# pcb_v2.net
KiCad netlist of a schematic drawn in EAGLE
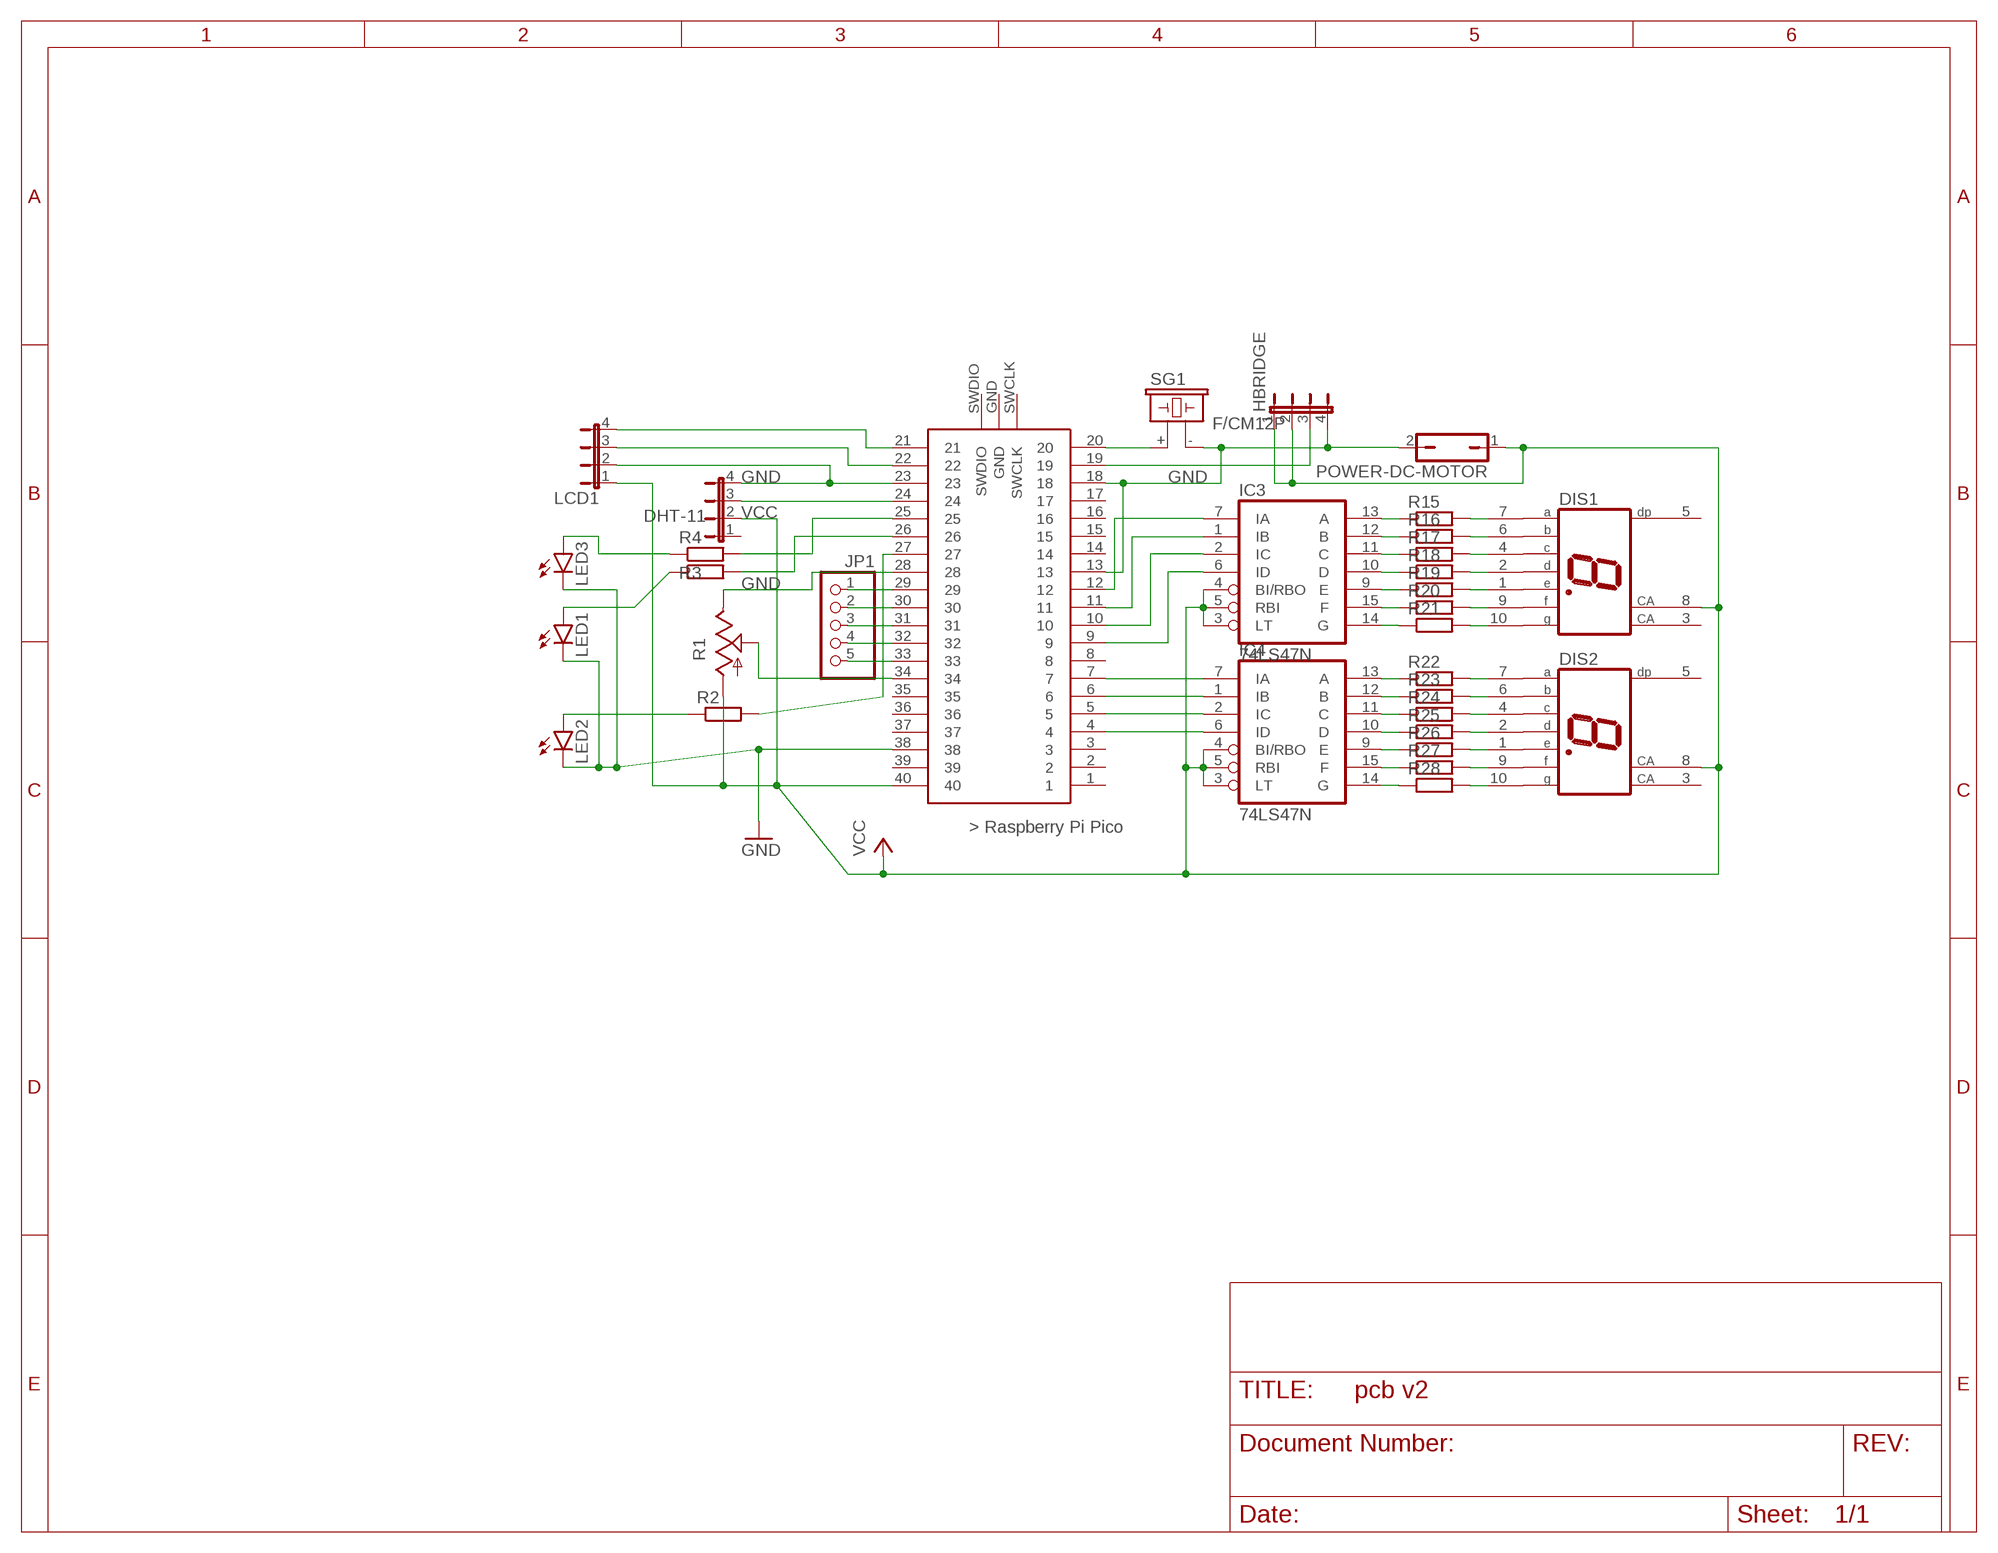
[diagram p0: schematic, sheet 1]

(export (version "E")
  (design (tool "Eeschema 10.0.6"))
  (components
    (comp (ref "DHT-11")
      (value "JP4E")
      (footprint "eagle-import:JP4")
      (libsource (lib "eagle-import") (part "JP4E"))
    )
    (comp (ref "DIS1")
      (value "HD-H101")
      (footprint "eagle-import:HDSP-M")
      (libsource (lib "eagle-import") (part "HD-H101"))
    )
    (comp (ref "DIS2")
      (value "HD-H101")
      (footprint "eagle-import:HDSP-M")
      (libsource (lib "eagle-import") (part "HD-H101"))
    )
    (comp (ref "HBRIDGE")
      (value "JP4E")
      (footprint "eagle-import:JP4")
      (libsource (lib "eagle-import") (part "JP4E"))
    )
    (comp (ref "IC3")
      (value "74LS47N")
      (footprint "eagle-import:DIL16")
      (libsource (lib "eagle-import") (part "7447NLS"))
    )
    (comp (ref "IC4")
      (value "74LS47N")
      (footprint "eagle-import:DIL16")
      (libsource (lib "eagle-import") (part "7447NLS"))
    )
    (comp (ref "JP1")
      (value "PINHD-1X5")
      (footprint "eagle-import:1X05")
      (libsource (lib "eagle-import") (part "PINHD-1X5"))
    )
    (comp (ref "LCD1")
      (value "JP4E")
      (footprint "eagle-import:JP4")
      (libsource (lib "eagle-import") (part "JP4E"))
    )
    (comp (ref "LED1")
      (value "LED5MM")
      (footprint "eagle-import:LED5MM")
      (libsource (lib "eagle-import") (part "LED5MM"))
    )
    (comp (ref "LED2")
      (value "LED5MM")
      (footprint "eagle-import:LED5MM")
      (libsource (lib "eagle-import") (part "LED5MM"))
    )
    (comp (ref "LED3")
      (value "LED5MM")
      (footprint "eagle-import:LED5MM")
      (libsource (lib "eagle-import") (part "LED5MM"))
    )
    (comp (ref "POWER-DC-MOTOR")
      (value "JP1Q")
      (footprint "eagle-import:JP1")
      (libsource (lib "eagle-import") (part "JP1Q"))
    )
    (comp (ref "R1")
      (value "TRIM_US-CA6V")
      (footprint "eagle-import:CA6V")
      (libsource (lib "eagle-import") (part "TRIM_US-CA6V"))
    )
    (comp (ref "R2")
      (value "R-EU_0207/10")
      (footprint "eagle-import:0207_10")
      (libsource (lib "eagle-import") (part "R-EU_0207/10"))
    )
    (comp (ref "R3")
      (value "R-EU_0207/10")
      (footprint "eagle-import:0207_10")
      (libsource (lib "eagle-import") (part "R-EU_0207/10"))
    )
    (comp (ref "R4")
      (value "R-EU_0207/10")
      (footprint "eagle-import:0207_10")
      (libsource (lib "eagle-import") (part "R-EU_0207/10"))
    )
    (comp (ref "R15")
      (value "R-EU_0207/12")
      (footprint "eagle-import:0207_12")
      (libsource (lib "eagle-import") (part "R-EU_0207/12"))
    )
    (comp (ref "R16")
      (value "R-EU_0207/12")
      (footprint "eagle-import:0207_12")
      (libsource (lib "eagle-import") (part "R-EU_0207/12"))
    )
    (comp (ref "R17")
      (value "R-EU_0207/12")
      (footprint "eagle-import:0207_12")
      (libsource (lib "eagle-import") (part "R-EU_0207/12"))
    )
    (comp (ref "R18")
      (value "R-EU_0207/12")
      (footprint "eagle-import:0207_12")
      (libsource (lib "eagle-import") (part "R-EU_0207/12"))
    )
    (comp (ref "R19")
      (value "R-EU_0207/12")
      (footprint "eagle-import:0207_12")
      (libsource (lib "eagle-import") (part "R-EU_0207/12"))
    )
    (comp (ref "R20")
      (value "R-EU_0207/12")
      (footprint "eagle-import:0207_12")
      (libsource (lib "eagle-import") (part "R-EU_0207/12"))
    )
    (comp (ref "R21")
      (value "R-EU_0207/12")
      (footprint "eagle-import:0207_12")
      (libsource (lib "eagle-import") (part "R-EU_0207/12"))
    )
    (comp (ref "R22")
      (value "R-EU_0207/12")
      (footprint "eagle-import:0207_12")
      (libsource (lib "eagle-import") (part "R-EU_0207/12"))
    )
    (comp (ref "R23")
      (value "R-EU_0207/12")
      (footprint "eagle-import:0207_12")
      (libsource (lib "eagle-import") (part "R-EU_0207/12"))
    )
    (comp (ref "R24")
      (value "R-EU_0207/12")
      (footprint "eagle-import:0207_12")
      (libsource (lib "eagle-import") (part "R-EU_0207/12"))
    )
    (comp (ref "R25")
      (value "R-EU_0207/12")
      (footprint "eagle-import:0207_12")
      (libsource (lib "eagle-import") (part "R-EU_0207/12"))
    )
    (comp (ref "R26")
      (value "R-EU_0207/12")
      (footprint "eagle-import:0207_12")
      (libsource (lib "eagle-import") (part "R-EU_0207/12"))
    )
    (comp (ref "R27")
      (value "R-EU_0207/12")
      (footprint "eagle-import:0207_12")
      (libsource (lib "eagle-import") (part "R-EU_0207/12"))
    )
    (comp (ref "R28")
      (value "R-EU_0207/12")
      (footprint "eagle-import:0207_12")
      (libsource (lib "eagle-import") (part "R-EU_0207/12"))
    )
    (comp (ref "SG1")
      (value "F/CM12P")
      (footprint "eagle-import:F_CM12P")
      (libsource (lib "eagle-import") (part "F/CM12P"))
    )
    (comp (ref "U$1")
      (value "RASPBERRY-PI-PICO_TH")
      (footprint "eagle-import:FT_RASPBERRY-PI-PICO_TH")
      (libsource (lib "eagle-import") (part "RASPBERRY-PI-PICO_TH"))
    )
  )
  (nets
    (net (code "1") (name "GND") (class "Default")
      (node (ref "DHT-11") (pin "4") (pinfunction "4_4") (pintype "passive"))
      (node (ref "HBRIDGE") (pin "4") (pinfunction "4_4") (pintype "passive"))
      (node (ref "LCD1") (pin "2") (pinfunction "2_2") (pintype "passive"))
      (node (ref "LED1") (pin "K") (pinfunction "C_K") (pintype "passive"))
      (node (ref "LED2") (pin "K") (pinfunction "C_K") (pintype "passive"))
      (node (ref "LED3") (pin "K") (pinfunction "C_K") (pintype "passive"))
      (node (ref "POWER-DC-MOTOR") (pin "2") (pinfunction "2_2") (pintype "passive"))
      (node (ref "R1") (pin "E") (pinfunction "E_E") (pintype "passive"))
      (node (ref "SG1") (pin "-") (pinfunction "2_-") (pintype "passive"))
      (node (ref "U$1") (pin "13") (pinfunction "13_13") (pintype "bidirectional"))
      (node (ref "U$1") (pin "18") (pinfunction "18_18") (pintype "bidirectional"))
      (node (ref "U$1") (pin "23") (pinfunction "23_23") (pintype "bidirectional"))
      (node (ref "U$1") (pin "28") (pinfunction "28_28") (pintype "bidirectional"))
      (node (ref "U$1") (pin "38") (pinfunction "38_38") (pintype "bidirectional"))
    )
    (net (code "2") (name "Net-(DHT-11-Pad3)") (class "Default")
      (node (ref "DHT-11") (pin "3") (pinfunction "3_3") (pintype "passive"))
      (node (ref "U$1") (pin "24") (pinfunction "24_24") (pintype "bidirectional"))
    )
    (net (code "3") (name "Net-(DIS1-A)") (class "Default")
      (node (ref "DIS1") (pin "7") (pinfunction "A_7") (pintype "passive"))
      (node (ref "R15") (pin "2") (pinfunction "2_2") (pintype "passive"))
    )
    (net (code "4") (name "Net-(DIS1-B)") (class "Default")
      (node (ref "DIS1") (pin "6") (pinfunction "B_6") (pintype "passive"))
      (node (ref "R16") (pin "2") (pinfunction "2_2") (pintype "passive"))
    )
    (net (code "5") (name "Net-(DIS1-C)") (class "Default")
      (node (ref "DIS1") (pin "4") (pinfunction "C_4") (pintype "passive"))
      (node (ref "R17") (pin "2") (pinfunction "2_2") (pintype "passive"))
    )
    (net (code "6") (name "Net-(DIS1-D)") (class "Default")
      (node (ref "DIS1") (pin "2") (pinfunction "D_2") (pintype "passive"))
      (node (ref "R18") (pin "2") (pinfunction "2_2") (pintype "passive"))
    )
    (net (code "7") (name "Net-(DIS1-E)") (class "Default")
      (node (ref "DIS1") (pin "1") (pinfunction "E_1") (pintype "passive"))
      (node (ref "R19") (pin "2") (pinfunction "2_2") (pintype "passive"))
    )
    (net (code "8") (name "Net-(DIS1-F)") (class "Default")
      (node (ref "DIS1") (pin "9") (pinfunction "F_9") (pintype "passive"))
      (node (ref "R20") (pin "2") (pinfunction "2_2") (pintype "passive"))
    )
    (net (code "9") (name "Net-(DIS1-G)") (class "Default")
      (node (ref "DIS1") (pin "10") (pinfunction "G_10") (pintype "passive"))
      (node (ref "R21") (pin "2") (pinfunction "2_2") (pintype "passive"))
    )
    (net (code "10") (name "Net-(DIS2-A)") (class "Default")
      (node (ref "DIS2") (pin "7") (pinfunction "A_7") (pintype "passive"))
      (node (ref "R22") (pin "2") (pinfunction "2_2") (pintype "passive"))
    )
    (net (code "11") (name "Net-(DIS2-B)") (class "Default")
      (node (ref "DIS2") (pin "6") (pinfunction "B_6") (pintype "passive"))
      (node (ref "R23") (pin "2") (pinfunction "2_2") (pintype "passive"))
    )
    (net (code "12") (name "Net-(DIS2-C)") (class "Default")
      (node (ref "DIS2") (pin "4") (pinfunction "C_4") (pintype "passive"))
      (node (ref "R24") (pin "2") (pinfunction "2_2") (pintype "passive"))
    )
    (net (code "13") (name "Net-(DIS2-D)") (class "Default")
      (node (ref "DIS2") (pin "2") (pinfunction "D_2") (pintype "passive"))
      (node (ref "R25") (pin "2") (pinfunction "2_2") (pintype "passive"))
    )
    (net (code "14") (name "Net-(DIS2-E)") (class "Default")
      (node (ref "DIS2") (pin "1") (pinfunction "E_1") (pintype "passive"))
      (node (ref "R26") (pin "2") (pinfunction "2_2") (pintype "passive"))
    )
    (net (code "15") (name "Net-(DIS2-F)") (class "Default")
      (node (ref "DIS2") (pin "9") (pinfunction "F_9") (pintype "passive"))
      (node (ref "R27") (pin "2") (pinfunction "2_2") (pintype "passive"))
    )
    (net (code "16") (name "Net-(DIS2-G)") (class "Default")
      (node (ref "DIS2") (pin "10") (pinfunction "G_10") (pintype "passive"))
      (node (ref "R28") (pin "2") (pinfunction "2_2") (pintype "passive"))
    )
    (net (code "17") (name "Net-(HBRIDGE-Pad3)") (class "Default")
      (node (ref "HBRIDGE") (pin "3") (pinfunction "3_3") (pintype "passive"))
      (node (ref "U$1") (pin "19") (pinfunction "19_19") (pintype "bidirectional"))
    )
    (net (code "18") (name "Net-(IC3A-A)") (class "Default")
      (node (ref "IC3") (pin "13") (pinfunction "A_13") (pintype "output"))
      (node (ref "R15") (pin "1") (pinfunction "1_1") (pintype "passive"))
    )
    (net (code "19") (name "Net-(IC3A-B)") (class "Default")
      (node (ref "IC3") (pin "12") (pinfunction "B_12") (pintype "output"))
      (node (ref "R16") (pin "1") (pinfunction "1_1") (pintype "passive"))
    )
    (net (code "20") (name "Net-(IC3A-C)") (class "Default")
      (node (ref "IC3") (pin "11") (pinfunction "C_11") (pintype "output"))
      (node (ref "R17") (pin "1") (pinfunction "1_1") (pintype "passive"))
    )
    (net (code "21") (name "Net-(IC3A-D)") (class "Default")
      (node (ref "IC3") (pin "10") (pinfunction "D_10") (pintype "output"))
      (node (ref "R18") (pin "1") (pinfunction "1_1") (pintype "passive"))
    )
    (net (code "22") (name "Net-(IC3A-E)") (class "Default")
      (node (ref "IC3") (pin "9") (pinfunction "E_9") (pintype "output"))
      (node (ref "R19") (pin "1") (pinfunction "1_1") (pintype "passive"))
    )
    (net (code "23") (name "Net-(IC3A-F)") (class "Default")
      (node (ref "IC3") (pin "15") (pinfunction "F_15") (pintype "output"))
      (node (ref "R20") (pin "1") (pinfunction "1_1") (pintype "passive"))
    )
    (net (code "24") (name "Net-(IC3A-G)") (class "Default")
      (node (ref "IC3") (pin "14") (pinfunction "G_14") (pintype "output"))
      (node (ref "R21") (pin "1") (pinfunction "1_1") (pintype "passive"))
    )
    (net (code "25") (name "Net-(IC3A-IA)") (class "Default")
      (node (ref "IC3") (pin "7") (pinfunction "IA_7") (pintype "input"))
      (node (ref "U$1") (pin "12") (pinfunction "12_12") (pintype "bidirectional"))
    )
    (net (code "26") (name "Net-(IC3A-IB)") (class "Default")
      (node (ref "IC3") (pin "1") (pinfunction "IB_1") (pintype "input"))
      (node (ref "U$1") (pin "11") (pinfunction "11_11") (pintype "bidirectional"))
    )
    (net (code "27") (name "Net-(IC3A-IC)") (class "Default")
      (node (ref "IC3") (pin "2") (pinfunction "IC_2") (pintype "input"))
      (node (ref "U$1") (pin "10") (pinfunction "10_10") (pintype "bidirectional"))
    )
    (net (code "28") (name "Net-(IC3A-ID)") (class "Default")
      (node (ref "IC3") (pin "6") (pinfunction "ID_6") (pintype "input"))
      (node (ref "U$1") (pin "9") (pinfunction "9_9") (pintype "bidirectional"))
    )
    (net (code "29") (name "Net-(IC4A-A)") (class "Default")
      (node (ref "IC4") (pin "13") (pinfunction "A_13") (pintype "output"))
      (node (ref "R22") (pin "1") (pinfunction "1_1") (pintype "passive"))
    )
    (net (code "30") (name "Net-(IC4A-B)") (class "Default")
      (node (ref "IC4") (pin "12") (pinfunction "B_12") (pintype "output"))
      (node (ref "R23") (pin "1") (pinfunction "1_1") (pintype "passive"))
    )
    (net (code "31") (name "Net-(IC4A-C)") (class "Default")
      (node (ref "IC4") (pin "11") (pinfunction "C_11") (pintype "output"))
      (node (ref "R24") (pin "1") (pinfunction "1_1") (pintype "passive"))
    )
    (net (code "32") (name "Net-(IC4A-D)") (class "Default")
      (node (ref "IC4") (pin "10") (pinfunction "D_10") (pintype "output"))
      (node (ref "R25") (pin "1") (pinfunction "1_1") (pintype "passive"))
    )
    (net (code "33") (name "Net-(IC4A-E)") (class "Default")
      (node (ref "IC4") (pin "9") (pinfunction "E_9") (pintype "output"))
      (node (ref "R26") (pin "1") (pinfunction "1_1") (pintype "passive"))
    )
    (net (code "34") (name "Net-(IC4A-F)") (class "Default")
      (node (ref "IC4") (pin "15") (pinfunction "F_15") (pintype "output"))
      (node (ref "R27") (pin "1") (pinfunction "1_1") (pintype "passive"))
    )
    (net (code "35") (name "Net-(IC4A-G)") (class "Default")
      (node (ref "IC4") (pin "14") (pinfunction "G_14") (pintype "output"))
      (node (ref "R28") (pin "1") (pinfunction "1_1") (pintype "passive"))
    )
    (net (code "36") (name "Net-(IC4A-IA)") (class "Default")
      (node (ref "IC4") (pin "7") (pinfunction "IA_7") (pintype "input"))
      (node (ref "U$1") (pin "7") (pinfunction "7_7") (pintype "bidirectional"))
    )
    (net (code "37") (name "Net-(IC4A-IB)") (class "Default")
      (node (ref "IC4") (pin "1") (pinfunction "IB_1") (pintype "input"))
      (node (ref "U$1") (pin "6") (pinfunction "6_6") (pintype "bidirectional"))
    )
    (net (code "38") (name "Net-(IC4A-IC)") (class "Default")
      (node (ref "IC4") (pin "2") (pinfunction "IC_2") (pintype "input"))
      (node (ref "U$1") (pin "5") (pinfunction "5_5") (pintype "bidirectional"))
    )
    (net (code "39") (name "Net-(IC4A-ID)") (class "Default")
      (node (ref "IC4") (pin "6") (pinfunction "ID_6") (pintype "input"))
      (node (ref "U$1") (pin "4") (pinfunction "4_4") (pintype "bidirectional"))
    )
    (net (code "40") (name "Net-(JP1-Pad1)") (class "Default")
      (node (ref "JP1") (pin "1") (pinfunction "1_1") (pintype "passive"))
      (node (ref "U$1") (pin "29") (pinfunction "29_29") (pintype "bidirectional"))
    )
    (net (code "41") (name "Net-(JP1-Pad2)") (class "Default")
      (node (ref "JP1") (pin "2") (pinfunction "2_2") (pintype "passive"))
      (node (ref "U$1") (pin "30") (pinfunction "30_30") (pintype "bidirectional"))
    )
    (net (code "42") (name "Net-(JP1-Pad3)") (class "Default")
      (node (ref "JP1") (pin "3") (pinfunction "3_3") (pintype "passive"))
      (node (ref "U$1") (pin "31") (pinfunction "31_31") (pintype "bidirectional"))
    )
    (net (code "43") (name "Net-(JP1-Pad4)") (class "Default")
      (node (ref "JP1") (pin "4") (pinfunction "4_4") (pintype "passive"))
      (node (ref "U$1") (pin "32") (pinfunction "32_32") (pintype "bidirectional"))
    )
    (net (code "44") (name "Net-(JP1-Pad5)") (class "Default")
      (node (ref "JP1") (pin "5") (pinfunction "5_5") (pintype "passive"))
      (node (ref "U$1") (pin "33") (pinfunction "33_33") (pintype "bidirectional"))
    )
    (net (code "45") (name "Net-(LCD1-Pad3)") (class "Default")
      (node (ref "LCD1") (pin "3") (pinfunction "3_3") (pintype "passive"))
      (node (ref "U$1") (pin "22") (pinfunction "22_22") (pintype "bidirectional"))
    )
    (net (code "46") (name "Net-(LCD1-Pad4)") (class "Default")
      (node (ref "LCD1") (pin "4") (pinfunction "4_4") (pintype "passive"))
      (node (ref "U$1") (pin "21") (pinfunction "21_21") (pintype "bidirectional"))
    )
    (net (code "47") (name "Net-(LED1-PadA)") (class "Default")
      (node (ref "LED1") (pin "A") (pinfunction "A_A") (pintype "passive"))
      (node (ref "R3") (pin "1") (pinfunction "1_1") (pintype "passive"))
    )
    (net (code "48") (name "Net-(LED2-PadA)") (class "Default")
      (node (ref "LED2") (pin "A") (pinfunction "A_A") (pintype "passive"))
      (node (ref "R2") (pin "1") (pinfunction "1_1") (pintype "passive"))
    )
    (net (code "49") (name "Net-(LED3-PadA)") (class "Default")
      (node (ref "LED3") (pin "A") (pinfunction "A_A") (pintype "passive"))
      (node (ref "R4") (pin "1") (pinfunction "1_1") (pintype "passive"))
    )
    (net (code "50") (name "Net-(R1-PadS)") (class "Default")
      (node (ref "R1") (pin "S") (pinfunction "S_S") (pintype "passive"))
      (node (ref "U$1") (pin "34") (pinfunction "34_34") (pintype "bidirectional"))
    )
    (net (code "51") (name "Net-(R2-Pad2)") (class "Default")
      (node (ref "R2") (pin "2") (pinfunction "2_2") (pintype "passive"))
      (node (ref "U$1") (pin "27") (pinfunction "27_27") (pintype "bidirectional"))
    )
    (net (code "52") (name "Net-(R3-Pad2)") (class "Default")
      (node (ref "R3") (pin "2") (pinfunction "2_2") (pintype "passive"))
      (node (ref "U$1") (pin "26") (pinfunction "26_26") (pintype "bidirectional"))
    )
    (net (code "53") (name "Net-(R4-Pad2)") (class "Default")
      (node (ref "R4") (pin "2") (pinfunction "2_2") (pintype "passive"))
      (node (ref "U$1") (pin "25") (pinfunction "25_25") (pintype "bidirectional"))
    )
    (net (code "54") (name "Net-(SG1-1)") (class "Default")
      (node (ref "SG1") (pin "+") (pinfunction "1_+") (pintype "passive"))
      (node (ref "U$1") (pin "20") (pinfunction "20_20") (pintype "bidirectional"))
    )
    (net (code "55") (name "VCC") (class "Default")
      (node (ref "DHT-11") (pin "2") (pinfunction "2_2") (pintype "passive"))
      (node (ref "DIS1") (pin "8") (pinfunction "CA_8") (pintype "passive"))
      (node (ref "DIS2") (pin "8") (pinfunction "CA_8") (pintype "passive"))
      (node (ref "HBRIDGE") (pin "1") (pinfunction "1_1") (pintype "passive"))
      (node (ref "HBRIDGE") (pin "2") (pinfunction "2_2") (pintype "passive"))
      (node (ref "IC3") (pin "3") (pinfunction "LT_3") (pintype "input"))
      (node (ref "IC3") (pin "4") (pinfunction "BI/RBO_4") (pintype "input"))
      (node (ref "IC3") (pin "5") (pinfunction "RBI_5") (pintype "input"))
      (node (ref "IC4") (pin "3") (pinfunction "LT_3") (pintype "input"))
      (node (ref "IC4") (pin "4") (pinfunction "BI/RBO_4") (pintype "input"))
      (node (ref "IC4") (pin "5") (pinfunction "RBI_5") (pintype "input"))
      (node (ref "LCD1") (pin "1") (pinfunction "1_1") (pintype "passive"))
      (node (ref "POWER-DC-MOTOR") (pin "1") (pinfunction "1_1") (pintype "passive"))
      (node (ref "R1") (pin "A") (pinfunction "A_A") (pintype "passive"))
      (node (ref "U$1") (pin "40") (pinfunction "40_40") (pintype "bidirectional"))
    )
    (net (code "56") (name "unconnected-(DHT-11-Pad1)") (class "Default")
      (node (ref "DHT-11") (pin "1") (pinfunction "1_1") (pintype "passive"))
    )
    (net (code "57") (name "unconnected-(DIS1-CA-Pad3)") (class "Default")
      (node (ref "DIS1") (pin "3") (pinfunction "CA_3") (pintype "passive"))
    )
    (net (code "58") (name "unconnected-(DIS1-DP-Pad5)") (class "Default")
      (node (ref "DIS1") (pin "5") (pinfunction "DP_5") (pintype "passive"))
    )
    (net (code "59") (name "unconnected-(DIS2-CA-Pad3)") (class "Default")
      (node (ref "DIS2") (pin "3") (pinfunction "CA_3") (pintype "passive"))
    )
    (net (code "60") (name "unconnected-(DIS2-DP-Pad5)") (class "Default")
      (node (ref "DIS2") (pin "5") (pinfunction "DP_5") (pintype "passive"))
    )
    (net (code "61") (name "unconnected-(U$1-Pad1)") (class "Default")
      (node (ref "U$1") (pin "1") (pinfunction "1_1") (pintype "bidirectional"))
    )
    (net (code "62") (name "unconnected-(U$1-Pad2)") (class "Default")
      (node (ref "U$1") (pin "2") (pinfunction "2_2") (pintype "bidirectional"))
    )
    (net (code "63") (name "unconnected-(U$1-Pad3)") (class "Default")
      (node (ref "U$1") (pin "3") (pinfunction "3_3") (pintype "bidirectional"))
    )
    (net (code "64") (name "unconnected-(U$1-Pad8)") (class "Default")
      (node (ref "U$1") (pin "8") (pinfunction "8_8") (pintype "bidirectional"))
    )
    (net (code "65") (name "unconnected-(U$1-Pad14)") (class "Default")
      (node (ref "U$1") (pin "14") (pinfunction "14_14") (pintype "bidirectional"))
    )
    (net (code "66") (name "unconnected-(U$1-Pad15)") (class "Default")
      (node (ref "U$1") (pin "15") (pinfunction "15_15") (pintype "bidirectional"))
    )
    (net (code "67") (name "unconnected-(U$1-Pad16)") (class "Default")
      (node (ref "U$1") (pin "16") (pinfunction "16_16") (pintype "bidirectional"))
    )
    (net (code "68") (name "unconnected-(U$1-Pad17)") (class "Default")
      (node (ref "U$1") (pin "17") (pinfunction "17_17") (pintype "bidirectional"))
    )
    (net (code "69") (name "unconnected-(U$1-Pad35)") (class "Default")
      (node (ref "U$1") (pin "35") (pinfunction "35_35") (pintype "bidirectional"))
    )
    (net (code "70") (name "unconnected-(U$1-Pad36)") (class "Default")
      (node (ref "U$1") (pin "36") (pinfunction "36_36") (pintype "bidirectional"))
    )
    (net (code "71") (name "unconnected-(U$1-Pad37)") (class "Default")
      (node (ref "U$1") (pin "37") (pinfunction "37_37") (pintype "bidirectional"))
    )
    (net (code "72") (name "unconnected-(U$1-Pad39)") (class "Default")
      (node (ref "U$1") (pin "39") (pinfunction "39_39") (pintype "bidirectional"))
    )
    (net (code "73") (name "unconnected-(U$1-PadGND)") (class "Default")
      (node (ref "U$1") (pin "GND") (pinfunction "GND_GND") (pintype "bidirectional"))
    )
    (net (code "74") (name "unconnected-(U$1-PadSWCLK)") (class "Default")
      (node (ref "U$1") (pin "SWCLK") (pinfunction "SWCLK_SWCLK") (pintype "bidirectional"))
    )
    (net (code "75") (name "unconnected-(U$1-PadSWDIO)") (class "Default")
      (node (ref "U$1") (pin "SWDIO") (pinfunction "SWDIO_SWDIO") (pintype "bidirectional"))
    )
  )
)
